# PCB-TLY-JACK_inverter.net
KiCad netlist of a schematic drawn in EAGLE
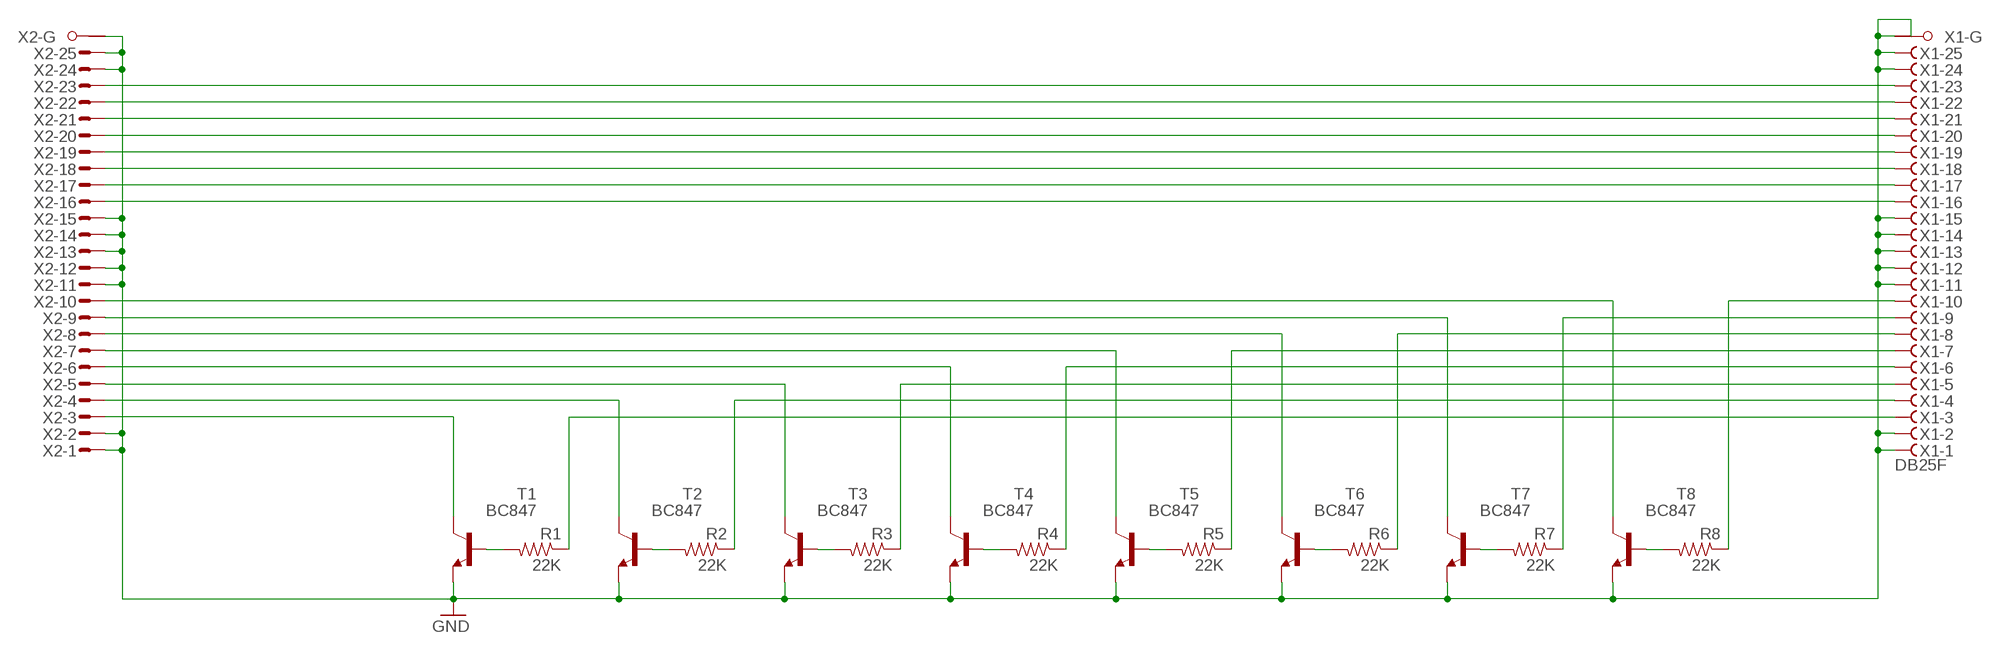
[diagram p0: schematic, sheet 1]

(export (version "E")
  (design (tool "Eeschema 10.0.6"))
  (components
    (comp (ref "R1")
      (value "22K")
      (footprint "eagle-import:0603-RES")
      (libsource (lib "eagle-import") (part "RESISTOR0603-RES"))
    )
    (comp (ref "R2")
      (value "22K")
      (footprint "eagle-import:0603-RES")
      (libsource (lib "eagle-import") (part "RESISTOR0603-RES"))
    )
    (comp (ref "R3")
      (value "22K")
      (footprint "eagle-import:0603-RES")
      (libsource (lib "eagle-import") (part "RESISTOR0603-RES"))
    )
    (comp (ref "R4")
      (value "22K")
      (footprint "eagle-import:0603-RES")
      (libsource (lib "eagle-import") (part "RESISTOR0603-RES"))
    )
    (comp (ref "R5")
      (value "22K")
      (footprint "eagle-import:0603-RES")
      (libsource (lib "eagle-import") (part "RESISTOR0603-RES"))
    )
    (comp (ref "R6")
      (value "22K")
      (footprint "eagle-import:0603-RES")
      (libsource (lib "eagle-import") (part "RESISTOR0603-RES"))
    )
    (comp (ref "R7")
      (value "22K")
      (footprint "eagle-import:0603-RES")
      (libsource (lib "eagle-import") (part "RESISTOR0603-RES"))
    )
    (comp (ref "R8")
      (value "22K")
      (footprint "eagle-import:0603-RES")
      (libsource (lib "eagle-import") (part "RESISTOR0603-RES"))
    )
    (comp (ref "T1")
      (value "BC847")
      (footprint "eagle-import:SOT23")
      (libsource (lib "eagle-import") (part "BC847"))
    )
    (comp (ref "T2")
      (value "BC847")
      (footprint "eagle-import:SOT23")
      (libsource (lib "eagle-import") (part "BC847"))
    )
    (comp (ref "T3")
      (value "BC847")
      (footprint "eagle-import:SOT23")
      (libsource (lib "eagle-import") (part "BC847"))
    )
    (comp (ref "T4")
      (value "BC847")
      (footprint "eagle-import:SOT23")
      (libsource (lib "eagle-import") (part "BC847"))
    )
    (comp (ref "T5")
      (value "BC847")
      (footprint "eagle-import:SOT23")
      (libsource (lib "eagle-import") (part "BC847"))
    )
    (comp (ref "T6")
      (value "BC847")
      (footprint "eagle-import:SOT23")
      (libsource (lib "eagle-import") (part "BC847"))
    )
    (comp (ref "T7")
      (value "BC847")
      (footprint "eagle-import:SOT23")
      (libsource (lib "eagle-import") (part "BC847"))
    )
    (comp (ref "T8")
      (value "BC847")
      (footprint "eagle-import:SOT23")
      (libsource (lib "eagle-import") (part "BC847"))
    )
    (comp (ref "X1")
      (value "DB25F")
      (footprint "eagle-import:F25HP")
      (libsource (lib "eagle-import") (part "F25HPS"))
    )
    (comp (ref "X2")
      (value "M25HPS")
      (footprint "eagle-import:M25HP")
      (libsource (lib "eagle-import") (part "M25HPS"))
    )
  )
  (nets
    (net (code "1") (name "GND") (class "Default")
      (node (ref "T1") (pin "2") (pinfunction "E_2") (pintype "passive"))
      (node (ref "T2") (pin "2") (pinfunction "E_2") (pintype "passive"))
      (node (ref "T3") (pin "2") (pinfunction "E_2") (pintype "passive"))
      (node (ref "T4") (pin "2") (pinfunction "E_2") (pintype "passive"))
      (node (ref "T5") (pin "2") (pinfunction "E_2") (pintype "passive"))
      (node (ref "T6") (pin "2") (pinfunction "E_2") (pintype "passive"))
      (node (ref "T7") (pin "2") (pinfunction "E_2") (pintype "passive"))
      (node (ref "T8") (pin "2") (pinfunction "E_2") (pintype "passive"))
      (node (ref "X1") (pin "1") (pinfunction "F_1") (pintype "passive"))
      (node (ref "X1") (pin "11") (pinfunction "F_11") (pintype "passive"))
      (node (ref "X1") (pin "12") (pinfunction "F_12") (pintype "passive"))
      (node (ref "X1") (pin "13") (pinfunction "F_13") (pintype "passive"))
      (node (ref "X1") (pin "14") (pinfunction "F_14") (pintype "passive"))
      (node (ref "X1") (pin "15") (pinfunction "F_15") (pintype "passive"))
      (node (ref "X1") (pin "2") (pinfunction "F_2") (pintype "passive"))
      (node (ref "X1") (pin "24") (pinfunction "F_24") (pintype "passive"))
      (node (ref "X1") (pin "25") (pinfunction "F_25") (pintype "passive"))
      (node (ref "X1") (pin "G1") (pinfunction "G1_G1") (pintype "passive"))
      (node (ref "X1") (pin "G2") (pinfunction "G2_G2") (pintype "passive"))
      (node (ref "X2") (pin "1") (pinfunction "M_1") (pintype "passive"))
      (node (ref "X2") (pin "11") (pinfunction "M_11") (pintype "passive"))
      (node (ref "X2") (pin "12") (pinfunction "M_12") (pintype "passive"))
      (node (ref "X2") (pin "13") (pinfunction "M_13") (pintype "passive"))
      (node (ref "X2") (pin "14") (pinfunction "M_14") (pintype "passive"))
      (node (ref "X2") (pin "15") (pinfunction "M_15") (pintype "passive"))
      (node (ref "X2") (pin "2") (pinfunction "M_2") (pintype "passive"))
      (node (ref "X2") (pin "24") (pinfunction "M_24") (pintype "passive"))
      (node (ref "X2") (pin "25") (pinfunction "M_25") (pintype "passive"))
      (node (ref "X2") (pin "G1") (pinfunction "G1_G1") (pintype "passive"))
    )
    (net (code "2") (name "Net-(T1-B)") (class "Default")
      (node (ref "R1") (pin "2") (pinfunction "2_2") (pintype "passive"))
      (node (ref "T1") (pin "1") (pinfunction "B_1") (pintype "passive"))
    )
    (net (code "3") (name "Net-(T1-C)") (class "Default")
      (node (ref "T1") (pin "3") (pinfunction "C_3") (pintype "passive"))
      (node (ref "X2") (pin "3") (pinfunction "M_3") (pintype "passive"))
    )
    (net (code "4") (name "Net-(T2-B)") (class "Default")
      (node (ref "R2") (pin "2") (pinfunction "2_2") (pintype "passive"))
      (node (ref "T2") (pin "1") (pinfunction "B_1") (pintype "passive"))
    )
    (net (code "5") (name "Net-(T2-C)") (class "Default")
      (node (ref "T2") (pin "3") (pinfunction "C_3") (pintype "passive"))
      (node (ref "X2") (pin "4") (pinfunction "M_4") (pintype "passive"))
    )
    (net (code "6") (name "Net-(T3-B)") (class "Default")
      (node (ref "R3") (pin "2") (pinfunction "2_2") (pintype "passive"))
      (node (ref "T3") (pin "1") (pinfunction "B_1") (pintype "passive"))
    )
    (net (code "7") (name "Net-(T3-C)") (class "Default")
      (node (ref "T3") (pin "3") (pinfunction "C_3") (pintype "passive"))
      (node (ref "X2") (pin "5") (pinfunction "M_5") (pintype "passive"))
    )
    (net (code "8") (name "Net-(T4-B)") (class "Default")
      (node (ref "R4") (pin "2") (pinfunction "2_2") (pintype "passive"))
      (node (ref "T4") (pin "1") (pinfunction "B_1") (pintype "passive"))
    )
    (net (code "9") (name "Net-(T4-C)") (class "Default")
      (node (ref "T4") (pin "3") (pinfunction "C_3") (pintype "passive"))
      (node (ref "X2") (pin "6") (pinfunction "M_6") (pintype "passive"))
    )
    (net (code "10") (name "Net-(T5-B)") (class "Default")
      (node (ref "R5") (pin "2") (pinfunction "2_2") (pintype "passive"))
      (node (ref "T5") (pin "1") (pinfunction "B_1") (pintype "passive"))
    )
    (net (code "11") (name "Net-(T5-C)") (class "Default")
      (node (ref "T5") (pin "3") (pinfunction "C_3") (pintype "passive"))
      (node (ref "X2") (pin "7") (pinfunction "M_7") (pintype "passive"))
    )
    (net (code "12") (name "Net-(T6-B)") (class "Default")
      (node (ref "R6") (pin "2") (pinfunction "2_2") (pintype "passive"))
      (node (ref "T6") (pin "1") (pinfunction "B_1") (pintype "passive"))
    )
    (net (code "13") (name "Net-(T6-C)") (class "Default")
      (node (ref "T6") (pin "3") (pinfunction "C_3") (pintype "passive"))
      (node (ref "X2") (pin "8") (pinfunction "M_8") (pintype "passive"))
    )
    (net (code "14") (name "Net-(T7-B)") (class "Default")
      (node (ref "R7") (pin "2") (pinfunction "2_2") (pintype "passive"))
      (node (ref "T7") (pin "1") (pinfunction "B_1") (pintype "passive"))
    )
    (net (code "15") (name "Net-(T7-C)") (class "Default")
      (node (ref "T7") (pin "3") (pinfunction "C_3") (pintype "passive"))
      (node (ref "X2") (pin "9") (pinfunction "M_9") (pintype "passive"))
    )
    (net (code "16") (name "Net-(T8-B)") (class "Default")
      (node (ref "R8") (pin "2") (pinfunction "2_2") (pintype "passive"))
      (node (ref "T8") (pin "1") (pinfunction "B_1") (pintype "passive"))
    )
    (net (code "17") (name "Net-(T8-C)") (class "Default")
      (node (ref "T8") (pin "3") (pinfunction "C_3") (pintype "passive"))
      (node (ref "X2") (pin "10") (pinfunction "M_10") (pintype "passive"))
    )
    (net (code "18") (name "Net-(X1B-F)") (class "Default")
      (node (ref "R8") (pin "1") (pinfunction "1_1") (pintype "passive"))
      (node (ref "X1") (pin "10") (pinfunction "F_10") (pintype "passive"))
    )
    (net (code "19") (name "Net-(X1H-F)") (class "Default")
      (node (ref "X1") (pin "16") (pinfunction "F_16") (pintype "passive"))
      (node (ref "X2") (pin "16") (pinfunction "M_16") (pintype "passive"))
    )
    (net (code "20") (name "Net-(X1I-F)") (class "Default")
      (node (ref "X1") (pin "17") (pinfunction "F_17") (pintype "passive"))
      (node (ref "X2") (pin "17") (pinfunction "M_17") (pintype "passive"))
    )
    (net (code "21") (name "Net-(X1J-F)") (class "Default")
      (node (ref "X1") (pin "18") (pinfunction "F_18") (pintype "passive"))
      (node (ref "X2") (pin "18") (pinfunction "M_18") (pintype "passive"))
    )
    (net (code "22") (name "Net-(X1K-F)") (class "Default")
      (node (ref "X1") (pin "19") (pinfunction "F_19") (pintype "passive"))
      (node (ref "X2") (pin "19") (pinfunction "M_19") (pintype "passive"))
    )
    (net (code "23") (name "Net-(X1M-F)") (class "Default")
      (node (ref "X1") (pin "20") (pinfunction "F_20") (pintype "passive"))
      (node (ref "X2") (pin "20") (pinfunction "M_20") (pintype "passive"))
    )
    (net (code "24") (name "Net-(X1N-F)") (class "Default")
      (node (ref "X1") (pin "21") (pinfunction "F_21") (pintype "passive"))
      (node (ref "X2") (pin "21") (pinfunction "M_21") (pintype "passive"))
    )
    (net (code "25") (name "Net-(X1O-F)") (class "Default")
      (node (ref "X1") (pin "22") (pinfunction "F_22") (pintype "passive"))
      (node (ref "X2") (pin "22") (pinfunction "M_22") (pintype "passive"))
    )
    (net (code "26") (name "Net-(X1P-F)") (class "Default")
      (node (ref "X1") (pin "23") (pinfunction "F_23") (pintype "passive"))
      (node (ref "X2") (pin "23") (pinfunction "M_23") (pintype "passive"))
    )
    (net (code "27") (name "Net-(X1S-F)") (class "Default")
      (node (ref "R1") (pin "1") (pinfunction "1_1") (pintype "passive"))
      (node (ref "X1") (pin "3") (pinfunction "F_3") (pintype "passive"))
    )
    (net (code "28") (name "Net-(X1T-F)") (class "Default")
      (node (ref "R2") (pin "1") (pinfunction "1_1") (pintype "passive"))
      (node (ref "X1") (pin "4") (pinfunction "F_4") (pintype "passive"))
    )
    (net (code "29") (name "Net-(X1U-F)") (class "Default")
      (node (ref "R3") (pin "1") (pinfunction "1_1") (pintype "passive"))
      (node (ref "X1") (pin "5") (pinfunction "F_5") (pintype "passive"))
    )
    (net (code "30") (name "Net-(X1V-F)") (class "Default")
      (node (ref "R4") (pin "1") (pinfunction "1_1") (pintype "passive"))
      (node (ref "X1") (pin "6") (pinfunction "F_6") (pintype "passive"))
    )
    (net (code "31") (name "Net-(X1W-F)") (class "Default")
      (node (ref "R5") (pin "1") (pinfunction "1_1") (pintype "passive"))
      (node (ref "X1") (pin "7") (pinfunction "F_7") (pintype "passive"))
    )
    (net (code "32") (name "Net-(X1X-F)") (class "Default")
      (node (ref "R6") (pin "1") (pinfunction "1_1") (pintype "passive"))
      (node (ref "X1") (pin "8") (pinfunction "F_8") (pintype "passive"))
    )
    (net (code "33") (name "Net-(X1Y-F)") (class "Default")
      (node (ref "R7") (pin "1") (pinfunction "1_1") (pintype "passive"))
      (node (ref "X1") (pin "9") (pinfunction "F_9") (pintype "passive"))
    )
    (net (code "34") (name "unconnected-(X2-PadG2)") (class "Default")
      (node (ref "X2") (pin "G2") (pinfunction "G2_G2") (pintype "passive"))
    )
  )
)
